# magnetometer.net
KiCad netlist of a schematic drawn in Altium Designer
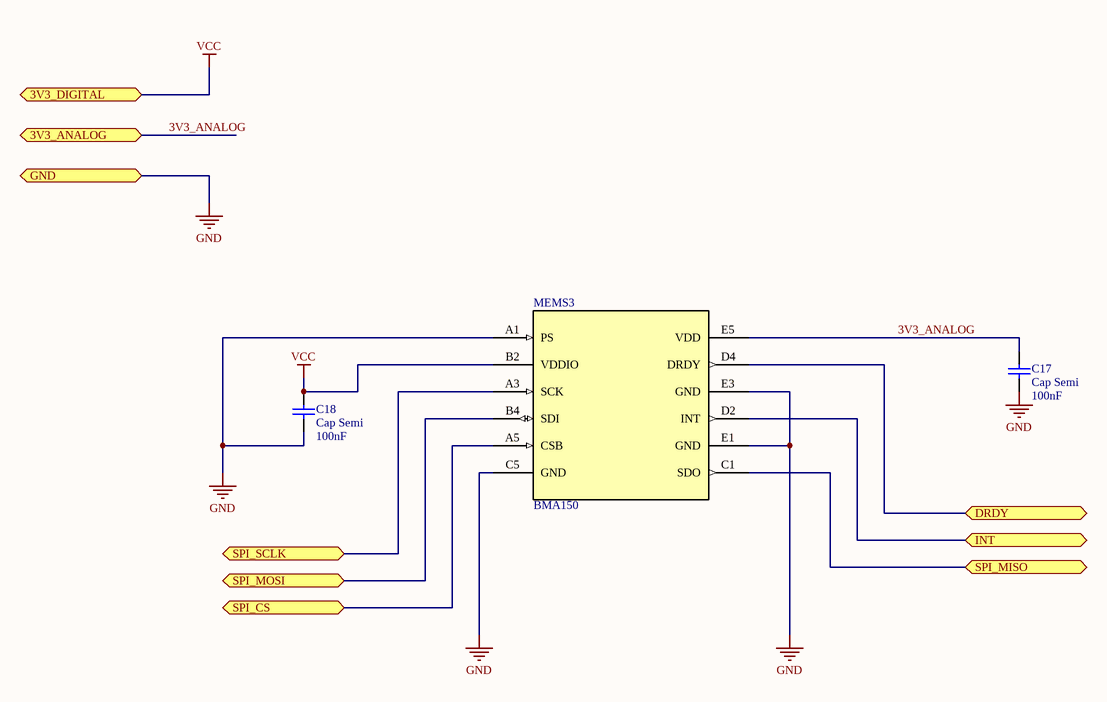
[diagram p0: magnetometer.SchDoc]

(export (version "E")
  (design (tool "Eeschema 10.0.6"))
  (components
    (comp (ref "C17")
      (value "Cap Semi")
      (footprint "C1206")
      (description "Capacitor (Semiconductor SIM Model)")
      (fields (field (name "ALTIUM_VALUE") "100nF") (field (name "PUBLISHER") "Altium Limited"))
      (libsource (lib "Miscellaneous Devices") (part "Cap Semi"))
    )
    (comp (ref "C18")
      (value "Cap Semi")
      (footprint "C1206")
      (description "Capacitor (Semiconductor SIM Model)")
      (fields (field (name "ALTIUM_VALUE") "100nF") (field (name "PUBLISHER") "Altium Limited"))
      (libsource (lib "Miscellaneous Devices") (part "Cap Semi"))
    )
    (comp (ref "MEMS3")
      (value "BMA150")
      (footprint "BGA12-BOSCH")
      (libsource (lib "RPi_sensor_expansion_board_library") (part "BMA150"))
    )
  )
  (nets
    (net (code "1") (name "/3V3_ANALOG") (class "Default")
      (node (ref "C17") (pin "2") (pinfunction "2_2") (pintype "passive"))
      (node (ref "MEMS3") (pin "E5") (pinfunction "VDD_E5") (pintype "power_in"))
    )
    (net (code "2") (name "/DRDY") (class "Default")
      (node (ref "MEMS3") (pin "D4") (pinfunction "DRDY_D4") (pintype "output"))
    )
    (net (code "3") (name "/INT") (class "Default")
      (node (ref "MEMS3") (pin "D2") (pinfunction "INT_D2") (pintype "output"))
    )
    (net (code "4") (name "/SPI_CS") (class "Default")
      (node (ref "MEMS3") (pin "A5") (pinfunction "CSB_A5") (pintype "input"))
    )
    (net (code "5") (name "/SPI_MISO") (class "Default")
      (node (ref "MEMS3") (pin "C1") (pinfunction "SDO_C1") (pintype "output"))
    )
    (net (code "6") (name "/SPI_MOSI") (class "Default")
      (node (ref "MEMS3") (pin "B4") (pinfunction "SDI_B4") (pintype "bidirectional"))
    )
    (net (code "7") (name "/SPI_SCLK") (class "Default")
      (node (ref "MEMS3") (pin "A3") (pinfunction "SCK_A3") (pintype "input"))
    )
    (net (code "8") (name "GND") (class "Default")
      (node (ref "C17") (pin "1") (pinfunction "1_1") (pintype "passive"))
      (node (ref "C18") (pin "1") (pinfunction "1_1") (pintype "passive"))
      (node (ref "MEMS3") (pin "A1") (pinfunction "PS_A1") (pintype "input"))
      (node (ref "MEMS3") (pin "C5") (pinfunction "GND_C5") (pintype "power_in"))
      (node (ref "MEMS3") (pin "E1") (pinfunction "GND_E1") (pintype "power_in"))
      (node (ref "MEMS3") (pin "E3") (pinfunction "GND_E3") (pintype "power_in"))
    )
    (net (code "9") (name "VCC") (class "Default")
      (node (ref "C18") (pin "2") (pinfunction "2_2") (pintype "passive"))
      (node (ref "MEMS3") (pin "B2") (pinfunction "VDDIO_B2") (pintype "power_in"))
    )
  )
)
